# transc_MIWI868.net
KiCad netlist of a schematic drawn in Altium Designer
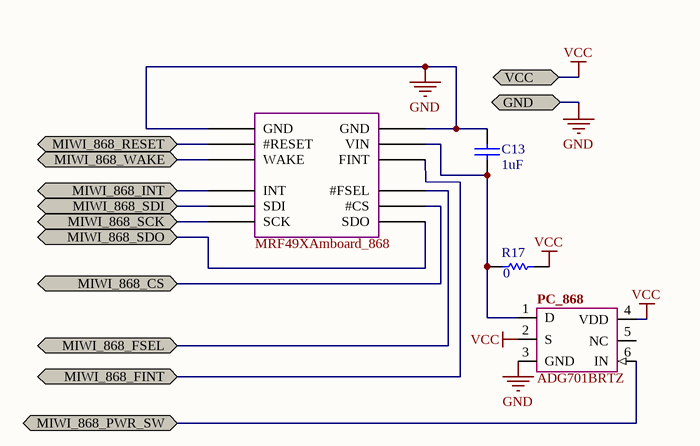
[diagram p0: transc_MIWI868.SchDoc]

(export (version "E")
  (design (tool "Eeschema 10.0.6"))
  (components
    (comp (ref "C13")
      (value "1uF")
      (footprint "1608[0603]")
      (description "Capacitor")
      (fields (field (name "Comment") "Cap") (field (name "PUBLISHER") "Altium Limited"))
      (libsource (lib "Miscellaneous Devices") (part "Cap"))
    )
    (comp (ref "MRF49XAmboard_868")
      (value "MRF49XAmboard")
      (footprint "MRF49XAmboard")
      (description "Microchip RF radio")
      (libsource (lib "agus_lib") (part "MRF49XAmboard"))
    )
    (comp (ref "PC_868")
      (value "ADG701BRTZ")
      (footprint "SOT23-6_L")
      (libsource (lib "PlacaBase_agus") (part "ADG701BRTZ"))
    )
    (comp (ref "R17")
      (value "0")
      (footprint "1608[0603]")
      (description "Resistor")
      (fields (field (name "Comment") "resistor") (field (name "PUBLISHER") "Altium Limited"))
      (libsource (lib "agus_lib") (part "RES"))
    )
  )
  (nets
    (net (code "1") (name "/MIWI_868_CS") (class "Default")
      (node (ref "MRF49XAmboard_868") (pin "8") (pinfunction "#CS_8") (pintype "passive"))
    )
    (net (code "2") (name "/MIWI_868_FINT") (class "Default")
      (node (ref "MRF49XAmboard_868") (pin "10") (pinfunction "FINT_10") (pintype "passive"))
    )
    (net (code "3") (name "/MIWI_868_FSEL") (class "Default")
      (node (ref "MRF49XAmboard_868") (pin "9") (pinfunction "#FSEL_9") (pintype "passive"))
    )
    (net (code "4") (name "/MIWI_868_INT") (class "Default")
      (node (ref "MRF49XAmboard_868") (pin "4") (pinfunction "INT_4") (pintype "passive"))
    )
    (net (code "5") (name "/MIWI_868_PWR_SW") (class "Default")
      (node (ref "PC_868") (pin "6") (pinfunction "IN_6") (pintype "input"))
    )
    (net (code "6") (name "/MIWI_868_RESET") (class "Default")
      (node (ref "MRF49XAmboard_868") (pin "2") (pinfunction "#RESET_2") (pintype "passive"))
    )
    (net (code "7") (name "/MIWI_868_SCK") (class "Default")
      (node (ref "MRF49XAmboard_868") (pin "6") (pinfunction "SCK_6") (pintype "passive"))
    )
    (net (code "8") (name "/MIWI_868_SDI") (class "Default")
      (node (ref "MRF49XAmboard_868") (pin "5") (pinfunction "SDI_5") (pintype "passive"))
    )
    (net (code "9") (name "/MIWI_868_SDO") (class "Default")
      (node (ref "MRF49XAmboard_868") (pin "7") (pinfunction "SDO_7") (pintype "passive"))
    )
    (net (code "10") (name "/MIWI_868_WAKE") (class "Default")
      (node (ref "MRF49XAmboard_868") (pin "3") (pinfunction "WAKE_3") (pintype "passive"))
    )
    (net (code "11") (name "GND") (class "Default")
      (node (ref "C13") (pin "1") (pinfunction "1_1") (pintype "passive"))
      (node (ref "MRF49XAmboard_868") (pin "1") (pinfunction "GND_1") (pintype "passive"))
      (node (ref "MRF49XAmboard_868") (pin "12") (pinfunction "GND_12") (pintype "passive"))
      (node (ref "PC_868") (pin "3") (pinfunction "GND_3") (pintype "passive"))
    )
    (net (code "12") (name "Net-(MRF49XAmboard_868-VIN)") (class "Default")
      (node (ref "C13") (pin "2") (pinfunction "2_2") (pintype "passive"))
      (node (ref "MRF49XAmboard_868") (pin "11") (pinfunction "VIN_11") (pintype "passive"))
      (node (ref "PC_868") (pin "1") (pinfunction "D_1") (pintype "bidirectional"))
      (node (ref "R17") (pin "2") (pinfunction "2_2") (pintype "passive"))
    )
    (net (code "13") (name "VCC") (class "Default")
      (node (ref "PC_868") (pin "2") (pinfunction "S_2") (pintype "bidirectional"))
      (node (ref "PC_868") (pin "4") (pinfunction "VDD_4") (pintype "power_in"))
      (node (ref "R17") (pin "1") (pinfunction "1_1") (pintype "passive"))
    )
    (net (code "14") (name "unconnected-(PC_868-NC-Pad5)") (class "Default")
      (node (ref "PC_868") (pin "5") (pinfunction "NC_5") (pintype "passive"))
    )
  )
)
